# R451X.net
KiCad netlist of a schematic drawn in EAGLE
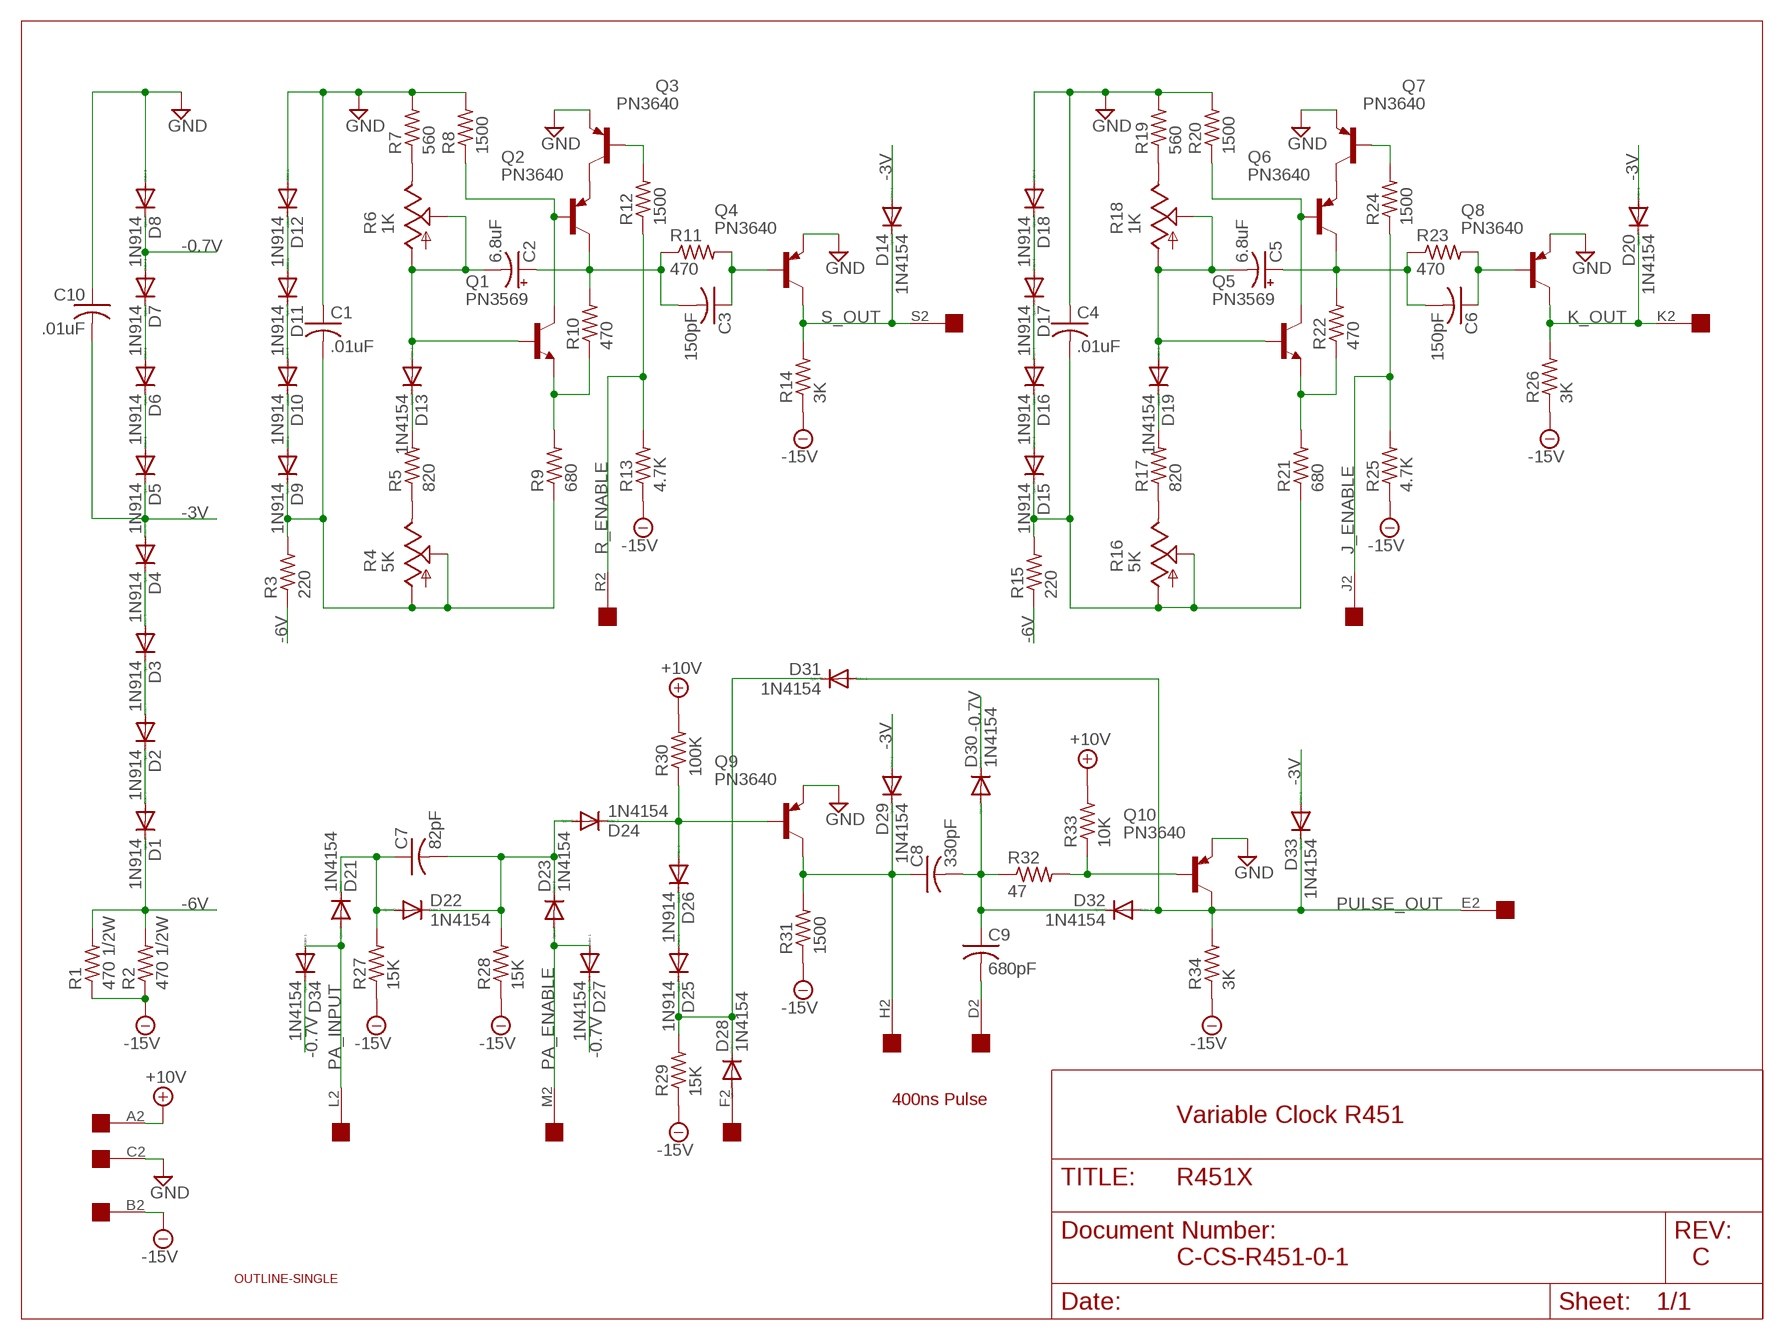
[diagram p0: schematic, sheet 1]

(export (version "E")
  (design (tool "Eeschema 10.0.6"))
  (components
    (comp (ref "C1")
      (value ".01uF")
      (footprint "eagle-import:C050-025X075")
      (libsource (lib "eagle-import") (part "C-US050-025X075"))
    )
    (comp (ref "C2")
      (value "6.8uF")
      (footprint "eagle-import:E12-4")
      (libsource (lib "eagle-import") (part "CPOL-USE12-4AXIAL"))
    )
    (comp (ref "C3")
      (value "150pF")
      (footprint "eagle-import:C075-032X103")
      (libsource (lib "eagle-import") (part "C-US075-032X103"))
    )
    (comp (ref "C4")
      (value ".01uF")
      (footprint "eagle-import:C050-025X075")
      (libsource (lib "eagle-import") (part "C-US050-025X075"))
    )
    (comp (ref "C5")
      (value "6.8uF")
      (footprint "eagle-import:E12-4")
      (libsource (lib "eagle-import") (part "CPOL-USE12-4AXIAL"))
    )
    (comp (ref "C6")
      (value "150pF")
      (footprint "eagle-import:C075-032X103")
      (libsource (lib "eagle-import") (part "C-US075-032X103"))
    )
    (comp (ref "C7")
      (value "82pF")
      (footprint "eagle-import:C075-032X103")
      (libsource (lib "eagle-import") (part "C-US075-032X103"))
    )
    (comp (ref "C8")
      (value "330pF")
      (footprint "eagle-import:C075-032X103")
      (libsource (lib "eagle-import") (part "C-US075-032X103"))
    )
    (comp (ref "C9")
      (value "680pF")
      (footprint "eagle-import:C075-032X103")
      (libsource (lib "eagle-import") (part "C-US075-032X103"))
    )
    (comp (ref "C10")
      (value ".01uF")
      (footprint "eagle-import:C050-025X075")
      (libsource (lib "eagle-import") (part "C-US050-025X075"))
    )
    (comp (ref "D1")
      (value "1N914")
      (footprint "eagle-import:DO35-10")
      (libsource (lib "eagle-import") (part "1N4148DO35-10"))
    )
    (comp (ref "D2")
      (value "1N914")
      (footprint "eagle-import:DO35-10")
      (libsource (lib "eagle-import") (part "1N4148DO35-10"))
    )
    (comp (ref "D3")
      (value "1N914")
      (footprint "eagle-import:DO35-10")
      (libsource (lib "eagle-import") (part "1N4148DO35-10"))
    )
    (comp (ref "D4")
      (value "1N914")
      (footprint "eagle-import:DO35-10")
      (libsource (lib "eagle-import") (part "1N4148DO35-10"))
    )
    (comp (ref "D5")
      (value "1N914")
      (footprint "eagle-import:DO35-10")
      (libsource (lib "eagle-import") (part "1N4148DO35-10"))
    )
    (comp (ref "D6")
      (value "1N914")
      (footprint "eagle-import:DO35-10")
      (libsource (lib "eagle-import") (part "1N4148DO35-10"))
    )
    (comp (ref "D7")
      (value "1N914")
      (footprint "eagle-import:DO35-10")
      (libsource (lib "eagle-import") (part "1N4148DO35-10"))
    )
    (comp (ref "D8")
      (value "1N914")
      (footprint "eagle-import:DO35-10")
      (libsource (lib "eagle-import") (part "1N4148DO35-10"))
    )
    (comp (ref "D9")
      (value "1N914")
      (footprint "eagle-import:DO35-10")
      (libsource (lib "eagle-import") (part "1N4148DO35-10"))
    )
    (comp (ref "D10")
      (value "1N914")
      (footprint "eagle-import:DO35-10")
      (libsource (lib "eagle-import") (part "1N4148DO35-10"))
    )
    (comp (ref "D11")
      (value "1N914")
      (footprint "eagle-import:DO35-10")
      (libsource (lib "eagle-import") (part "1N4148DO35-10"))
    )
    (comp (ref "D12")
      (value "1N914")
      (footprint "eagle-import:DO35-10")
      (libsource (lib "eagle-import") (part "1N4148DO35-10"))
    )
    (comp (ref "D13")
      (value "1N4154")
      (footprint "eagle-import:DO35-10")
      (libsource (lib "eagle-import") (part "1N4148DO35-10"))
    )
    (comp (ref "D14")
      (value "1N4154")
      (footprint "eagle-import:DO35-10")
      (libsource (lib "eagle-import") (part "1N4148DO35-10"))
    )
    (comp (ref "D15")
      (value "1N914")
      (footprint "eagle-import:DO35-10")
      (libsource (lib "eagle-import") (part "1N4148DO35-10"))
    )
    (comp (ref "D16")
      (value "1N914")
      (footprint "eagle-import:DO35-10")
      (libsource (lib "eagle-import") (part "1N4148DO35-10"))
    )
    (comp (ref "D17")
      (value "1N914")
      (footprint "eagle-import:DO35-10")
      (libsource (lib "eagle-import") (part "1N4148DO35-10"))
    )
    (comp (ref "D18")
      (value "1N914")
      (footprint "eagle-import:DO35-10")
      (libsource (lib "eagle-import") (part "1N4148DO35-10"))
    )
    (comp (ref "D19")
      (value "1N4154")
      (footprint "eagle-import:DO35-10")
      (libsource (lib "eagle-import") (part "1N4148DO35-10"))
    )
    (comp (ref "D20")
      (value "1N4154")
      (footprint "eagle-import:DO35-10")
      (libsource (lib "eagle-import") (part "1N4148DO35-10"))
    )
    (comp (ref "D21")
      (value "1N4154")
      (footprint "eagle-import:DO35-10")
      (libsource (lib "eagle-import") (part "1N4148DO35-10"))
    )
    (comp (ref "D22")
      (value "1N4154")
      (footprint "eagle-import:DO35-10")
      (libsource (lib "eagle-import") (part "1N4148DO35-10"))
    )
    (comp (ref "D23")
      (value "1N4154")
      (footprint "eagle-import:DO35-10")
      (libsource (lib "eagle-import") (part "1N4148DO35-10"))
    )
    (comp (ref "D24")
      (value "1N4154")
      (footprint "eagle-import:DO35-10")
      (libsource (lib "eagle-import") (part "1N4148DO35-10"))
    )
    (comp (ref "D25")
      (value "1N914")
      (footprint "eagle-import:DO35-10")
      (libsource (lib "eagle-import") (part "1N4148DO35-10"))
    )
    (comp (ref "D26")
      (value "1N914")
      (footprint "eagle-import:DO35-10")
      (libsource (lib "eagle-import") (part "1N4148DO35-10"))
    )
    (comp (ref "D27")
      (value "1N4154")
      (footprint "eagle-import:DO35-10")
      (libsource (lib "eagle-import") (part "1N4148DO35-10"))
    )
    (comp (ref "D28")
      (value "1N4154")
      (footprint "eagle-import:DO35-10")
      (libsource (lib "eagle-import") (part "1N4148DO35-10"))
    )
    (comp (ref "D29")
      (value "1N4154")
      (footprint "eagle-import:DO35-10")
      (libsource (lib "eagle-import") (part "1N4148DO35-10"))
    )
    (comp (ref "D30")
      (value "1N4154")
      (footprint "eagle-import:DO35-10")
      (libsource (lib "eagle-import") (part "1N4148DO35-10"))
    )
    (comp (ref "D31")
      (value "1N4154")
      (footprint "eagle-import:DO35-10")
      (libsource (lib "eagle-import") (part "1N4148DO35-10"))
    )
    (comp (ref "D32")
      (value "1N4154")
      (footprint "eagle-import:DO35-10")
      (libsource (lib "eagle-import") (part "1N4148DO35-10"))
    )
    (comp (ref "D33")
      (value "1N4154")
      (footprint "eagle-import:DO35-10")
      (libsource (lib "eagle-import") (part "1N4148DO35-10"))
    )
    (comp (ref "D34")
      (value "1N4154")
      (footprint "eagle-import:DO35-10")
      (libsource (lib "eagle-import") (part "1N4148DO35-10"))
    )
    (comp (ref "Q1")
      (value "PN3569")
      (footprint "eagle-import:TO5")
      (libsource (lib "eagle-import") (part "2N2102"))
    )
    (comp (ref "Q2")
      (value "PN3640")
      (footprint "eagle-import:TO39")
      (libsource (lib "eagle-import") (part "2N2904"))
    )
    (comp (ref "Q3")
      (value "PN3640")
      (footprint "eagle-import:TO39")
      (libsource (lib "eagle-import") (part "2N2904"))
    )
    (comp (ref "Q4")
      (value "PN3640")
      (footprint "eagle-import:TO39")
      (libsource (lib "eagle-import") (part "2N2904"))
    )
    (comp (ref "Q5")
      (value "PN3569")
      (footprint "eagle-import:TO5")
      (libsource (lib "eagle-import") (part "2N2102"))
    )
    (comp (ref "Q6")
      (value "PN3640")
      (footprint "eagle-import:TO39")
      (libsource (lib "eagle-import") (part "2N2904"))
    )
    (comp (ref "Q7")
      (value "PN3640")
      (footprint "eagle-import:TO39")
      (libsource (lib "eagle-import") (part "2N2904"))
    )
    (comp (ref "Q8")
      (value "PN3640")
      (footprint "eagle-import:TO39")
      (libsource (lib "eagle-import") (part "2N2904"))
    )
    (comp (ref "Q9")
      (value "PN3640")
      (footprint "eagle-import:TO39")
      (libsource (lib "eagle-import") (part "2N2904"))
    )
    (comp (ref "Q10")
      (value "PN3640")
      (footprint "eagle-import:TO39")
      (libsource (lib "eagle-import") (part "2N2904"))
    )
    (comp (ref "R1")
      (value "470 1/2W")
      (footprint "eagle-import:0411_15")
      (libsource (lib "eagle-import") (part "R-US_0411/15"))
    )
    (comp (ref "R2")
      (value "470 1/2W")
      (footprint "eagle-import:0411_15")
      (libsource (lib "eagle-import") (part "R-US_0411/15"))
    )
    (comp (ref "R3")
      (value "220")
      (footprint "eagle-import:0207_10")
      (libsource (lib "eagle-import") (part "R-US_0207/10"))
    )
    (comp (ref "R4")
      (value "5K")
      (footprint "eagle-import:CT6")
      (libsource (lib "eagle-import") (part "TRIM_US-CT6"))
    )
    (comp (ref "R5")
      (value "820")
      (footprint "eagle-import:0207_10")
      (libsource (lib "eagle-import") (part "R-US_0207/10"))
    )
    (comp (ref "R6")
      (value "1K")
      (footprint "eagle-import:CT6")
      (libsource (lib "eagle-import") (part "TRIM_US-CT6"))
    )
    (comp (ref "R7")
      (value "560")
      (footprint "eagle-import:0207_10")
      (libsource (lib "eagle-import") (part "R-US_0207/10"))
    )
    (comp (ref "R8")
      (value "1500")
      (footprint "eagle-import:0207_10")
      (libsource (lib "eagle-import") (part "R-US_0207/10"))
    )
    (comp (ref "R9")
      (value "680")
      (footprint "eagle-import:0207_10")
      (libsource (lib "eagle-import") (part "R-US_0207/10"))
    )
    (comp (ref "R10")
      (value "470")
      (footprint "eagle-import:0207_10")
      (libsource (lib "eagle-import") (part "R-US_0207/10"))
    )
    (comp (ref "R11")
      (value "470")
      (footprint "eagle-import:0207_10")
      (libsource (lib "eagle-import") (part "R-US_0207/10"))
    )
    (comp (ref "R12")
      (value "1500")
      (footprint "eagle-import:0207_10")
      (libsource (lib "eagle-import") (part "R-US_0207/10"))
    )
    (comp (ref "R13")
      (value "4.7K")
      (footprint "eagle-import:0207_10")
      (libsource (lib "eagle-import") (part "R-US_0207/10"))
    )
    (comp (ref "R14")
      (value "3K")
      (footprint "eagle-import:0207_10")
      (libsource (lib "eagle-import") (part "R-US_0207/10"))
    )
    (comp (ref "R15")
      (value "220")
      (footprint "eagle-import:0207_10")
      (libsource (lib "eagle-import") (part "R-US_0207/10"))
    )
    (comp (ref "R16")
      (value "5K")
      (footprint "eagle-import:CT6")
      (libsource (lib "eagle-import") (part "TRIM_US-CT6"))
    )
    (comp (ref "R17")
      (value "820")
      (footprint "eagle-import:0207_10")
      (libsource (lib "eagle-import") (part "R-US_0207/10"))
    )
    (comp (ref "R18")
      (value "1K")
      (footprint "eagle-import:CT6")
      (libsource (lib "eagle-import") (part "TRIM_US-CT6"))
    )
    (comp (ref "R19")
      (value "560")
      (footprint "eagle-import:0207_10")
      (libsource (lib "eagle-import") (part "R-US_0207/10"))
    )
    (comp (ref "R20")
      (value "1500")
      (footprint "eagle-import:0207_10")
      (libsource (lib "eagle-import") (part "R-US_0207/10"))
    )
    (comp (ref "R21")
      (value "680")
      (footprint "eagle-import:0207_10")
      (libsource (lib "eagle-import") (part "R-US_0207/10"))
    )
    (comp (ref "R22")
      (value "470")
      (footprint "eagle-import:0207_10")
      (libsource (lib "eagle-import") (part "R-US_0207/10"))
    )
    (comp (ref "R23")
      (value "470")
      (footprint "eagle-import:0207_10")
      (libsource (lib "eagle-import") (part "R-US_0207/10"))
    )
    (comp (ref "R24")
      (value "1500")
      (footprint "eagle-import:0207_10")
      (libsource (lib "eagle-import") (part "R-US_0207/10"))
    )
    (comp (ref "R25")
      (value "4.7K")
      (footprint "eagle-import:0207_10")
      (libsource (lib "eagle-import") (part "R-US_0207/10"))
    )
    (comp (ref "R26")
      (value "3K")
      (footprint "eagle-import:0207_10")
      (libsource (lib "eagle-import") (part "R-US_0207/10"))
    )
    (comp (ref "R27")
      (value "15K")
      (footprint "eagle-import:0207_10")
      (libsource (lib "eagle-import") (part "R-US_0207/10"))
    )
    (comp (ref "R28")
      (value "15K")
      (footprint "eagle-import:0207_10")
      (libsource (lib "eagle-import") (part "R-US_0207/10"))
    )
    (comp (ref "R29")
      (value "15K")
      (footprint "eagle-import:0207_10")
      (libsource (lib "eagle-import") (part "R-US_0207/10"))
    )
    (comp (ref "R30")
      (value "100K")
      (footprint "eagle-import:0207_10")
      (libsource (lib "eagle-import") (part "R-US_0207/10"))
    )
    (comp (ref "R31")
      (value "1500")
      (footprint "eagle-import:0207_10")
      (libsource (lib "eagle-import") (part "R-US_0207/10"))
    )
    (comp (ref "R32")
      (value "47")
      (footprint "eagle-import:0207_10")
      (libsource (lib "eagle-import") (part "R-US_0207/10"))
    )
    (comp (ref "R33")
      (value "10K")
      (footprint "eagle-import:0207_10")
      (libsource (lib "eagle-import") (part "R-US_0207/10"))
    )
    (comp (ref "R34")
      (value "3K")
      (footprint "eagle-import:0207_10")
      (libsource (lib "eagle-import") (part "R-US_0207/10"))
    )
    (comp (ref "U$1")
      (value "OUTLINE-SINGLE")
      (footprint "eagle-import:SINGLE")
      (libsource (lib "eagle-import") (part "OUTLINE-SINGLE"))
    )
    (comp (ref "U$2")
      (value "EDGE-1")
      (footprint "eagle-import:EDGE-CON1")
      (libsource (lib "eagle-import") (part "EDGE-1"))
    )
  )
  (nets
    (net (code "1") (name "+10V") (class "Default")
      (node (ref "R30") (pin "2") (pinfunction "2_2") (pintype "passive"))
      (node (ref "R33") (pin "2") (pinfunction "2_2") (pintype "passive"))
      (node (ref "U$2") (pin "A2") (pinfunction "1_A2") (pintype "bidirectional"))
    )
    (net (code "2") (name "-15V") (class "Default")
      (node (ref "R1") (pin "1") (pinfunction "1_1") (pintype "passive"))
      (node (ref "R13") (pin "1") (pinfunction "1_1") (pintype "passive"))
      (node (ref "R14") (pin "1") (pinfunction "1_1") (pintype "passive"))
      (node (ref "R2") (pin "1") (pinfunction "1_1") (pintype "passive"))
      (node (ref "R25") (pin "1") (pinfunction "1_1") (pintype "passive"))
      (node (ref "R26") (pin "1") (pinfunction "1_1") (pintype "passive"))
      (node (ref "R27") (pin "1") (pinfunction "1_1") (pintype "passive"))
      (node (ref "R28") (pin "1") (pinfunction "1_1") (pintype "passive"))
      (node (ref "R29") (pin "1") (pinfunction "1_1") (pintype "passive"))
      (node (ref "R31") (pin "1") (pinfunction "1_1") (pintype "passive"))
      (node (ref "R34") (pin "1") (pinfunction "1_1") (pintype "passive"))
      (node (ref "U$2") (pin "B2") (pinfunction "1_B2") (pintype "bidirectional"))
    )
    (net (code "3") (name "/-0.7V") (class "Default")
      (node (ref "D27") (pin "C") (pinfunction "C_C") (pintype "passive"))
      (node (ref "D30") (pin "C") (pinfunction "C_C") (pintype "passive"))
      (node (ref "D34") (pin "C") (pinfunction "C_C") (pintype "passive"))
      (node (ref "D7") (pin "A") (pinfunction "A_A") (pintype "passive"))
      (node (ref "D8") (pin "C") (pinfunction "C_C") (pintype "passive"))
    )
    (net (code "4") (name "/-3V") (class "Default")
      (node (ref "C10") (pin "2") (pinfunction "2_2") (pintype "passive"))
      (node (ref "D14") (pin "A") (pinfunction "A_A") (pintype "passive"))
      (node (ref "D20") (pin "A") (pinfunction "A_A") (pintype "passive"))
      (node (ref "D29") (pin "A") (pinfunction "A_A") (pintype "passive"))
      (node (ref "D33") (pin "A") (pinfunction "A_A") (pintype "passive"))
      (node (ref "D4") (pin "A") (pinfunction "A_A") (pintype "passive"))
      (node (ref "D5") (pin "C") (pinfunction "C_C") (pintype "passive"))
    )
    (net (code "5") (name "/-6V") (class "Default")
      (node (ref "D1") (pin "C") (pinfunction "C_C") (pintype "passive"))
      (node (ref "R1") (pin "2") (pinfunction "2_2") (pintype "passive"))
      (node (ref "R15") (pin "1") (pinfunction "1_1") (pintype "passive"))
      (node (ref "R2") (pin "2") (pinfunction "2_2") (pintype "passive"))
      (node (ref "R3") (pin "1") (pinfunction "1_1") (pintype "passive"))
    )
    (net (code "6") (name "/J_ENABLE") (class "Default")
      (node (ref "R24") (pin "1") (pinfunction "1_1") (pintype "passive"))
      (node (ref "R25") (pin "2") (pinfunction "2_2") (pintype "passive"))
      (node (ref "U$2") (pin "J2") (pinfunction "1_J2") (pintype "bidirectional"))
    )
    (net (code "7") (name "/K_OUT") (class "Default")
      (node (ref "D20") (pin "C") (pinfunction "C_C") (pintype "passive"))
      (node (ref "Q8") (pin "3") (pinfunction "C_3") (pintype "passive"))
      (node (ref "R26") (pin "2") (pinfunction "2_2") (pintype "passive"))
      (node (ref "U$2") (pin "K2") (pinfunction "1_K2") (pintype "bidirectional"))
    )
    (net (code "8") (name "/PA_ENABLE") (class "Default")
      (node (ref "D23") (pin "A") (pinfunction "A_A") (pintype "passive"))
      (node (ref "D27") (pin "A") (pinfunction "A_A") (pintype "passive"))
      (node (ref "U$2") (pin "M2") (pinfunction "1_M2") (pintype "bidirectional"))
    )
    (net (code "9") (name "/PA_INPUT") (class "Default")
      (node (ref "D21") (pin "A") (pinfunction "A_A") (pintype "passive"))
      (node (ref "D34") (pin "A") (pinfunction "A_A") (pintype "passive"))
      (node (ref "U$2") (pin "L2") (pinfunction "1_L2") (pintype "bidirectional"))
    )
    (net (code "10") (name "/PULSE_OUT") (class "Default")
      (node (ref "D31") (pin "A") (pinfunction "A_A") (pintype "passive"))
      (node (ref "D32") (pin "A") (pinfunction "A_A") (pintype "passive"))
      (node (ref "D33") (pin "C") (pinfunction "C_C") (pintype "passive"))
      (node (ref "Q10") (pin "3") (pinfunction "C_3") (pintype "passive"))
      (node (ref "R34") (pin "2") (pinfunction "2_2") (pintype "passive"))
      (node (ref "U$2") (pin "E2") (pinfunction "1_E2") (pintype "bidirectional"))
    )
    (net (code "11") (name "/R_ENABLE") (class "Default")
      (node (ref "R12") (pin "1") (pinfunction "1_1") (pintype "passive"))
      (node (ref "R13") (pin "2") (pinfunction "2_2") (pintype "passive"))
      (node (ref "U$2") (pin "R2") (pinfunction "1_R2") (pintype "bidirectional"))
    )
    (net (code "12") (name "/S_OUT") (class "Default")
      (node (ref "D14") (pin "C") (pinfunction "C_C") (pintype "passive"))
      (node (ref "Q4") (pin "3") (pinfunction "C_3") (pintype "passive"))
      (node (ref "R14") (pin "2") (pinfunction "2_2") (pintype "passive"))
      (node (ref "U$2") (pin "S2") (pinfunction "1_S2") (pintype "bidirectional"))
    )
    (net (code "13") (name "GND") (class "Default")
      (node (ref "C1") (pin "1") (pinfunction "1_1") (pintype "passive"))
      (node (ref "C10") (pin "1") (pinfunction "1_1") (pintype "passive"))
      (node (ref "C4") (pin "1") (pinfunction "1_1") (pintype "passive"))
      (node (ref "D12") (pin "A") (pinfunction "A_A") (pintype "passive"))
      (node (ref "D18") (pin "A") (pinfunction "A_A") (pintype "passive"))
      (node (ref "D8") (pin "A") (pinfunction "A_A") (pintype "passive"))
      (node (ref "Q10") (pin "1") (pinfunction "E_1") (pintype "passive"))
      (node (ref "Q3") (pin "1") (pinfunction "E_1") (pintype "passive"))
      (node (ref "Q4") (pin "1") (pinfunction "E_1") (pintype "passive"))
      (node (ref "Q7") (pin "1") (pinfunction "E_1") (pintype "passive"))
      (node (ref "Q8") (pin "1") (pinfunction "E_1") (pintype "passive"))
      (node (ref "Q9") (pin "1") (pinfunction "E_1") (pintype "passive"))
      (node (ref "R19") (pin "2") (pinfunction "2_2") (pintype "passive"))
      (node (ref "R20") (pin "2") (pinfunction "2_2") (pintype "passive"))
      (node (ref "R7") (pin "2") (pinfunction "2_2") (pintype "passive"))
      (node (ref "R8") (pin "2") (pinfunction "2_2") (pintype "passive"))
      (node (ref "U$2") (pin "C2") (pinfunction "1_C2") (pintype "bidirectional"))
    )
    (net (code "14") (name "Net-(C1-Pad2)") (class "Default")
      (node (ref "C1") (pin "2") (pinfunction "2_2") (pintype "passive"))
      (node (ref "D9") (pin "C") (pinfunction "C_C") (pintype "passive"))
      (node (ref "R3") (pin "2") (pinfunction "2_2") (pintype "passive"))
      (node (ref "R4") (pin "A") (pinfunction "A_A") (pintype "passive"))
      (node (ref "R4") (pin "S") (pinfunction "S_S") (pintype "passive"))
      (node (ref "R9") (pin "1") (pinfunction "1_1") (pintype "passive"))
    )
    (net (code "15") (name "Net-(C4-Pad2)") (class "Default")
      (node (ref "C4") (pin "2") (pinfunction "2_2") (pintype "passive"))
      (node (ref "D15") (pin "C") (pinfunction "C_C") (pintype "passive"))
      (node (ref "R15") (pin "2") (pinfunction "2_2") (pintype "passive"))
      (node (ref "R16") (pin "A") (pinfunction "A_A") (pintype "passive"))
      (node (ref "R16") (pin "S") (pinfunction "S_S") (pintype "passive"))
      (node (ref "R21") (pin "1") (pinfunction "1_1") (pintype "passive"))
    )
    (net (code "16") (name "Net-(C7-Pad1)") (class "Default")
      (node (ref "C7") (pin "1") (pinfunction "1_1") (pintype "passive"))
      (node (ref "D21") (pin "C") (pinfunction "C_C") (pintype "passive"))
      (node (ref "D22") (pin "A") (pinfunction "A_A") (pintype "passive"))
      (node (ref "R27") (pin "2") (pinfunction "2_2") (pintype "passive"))
    )
    (net (code "17") (name "Net-(C7-Pad2)") (class "Default")
      (node (ref "C7") (pin "2") (pinfunction "2_2") (pintype "passive"))
      (node (ref "D22") (pin "C") (pinfunction "C_C") (pintype "passive"))
      (node (ref "D23") (pin "C") (pinfunction "C_C") (pintype "passive"))
      (node (ref "D24") (pin "A") (pinfunction "A_A") (pintype "passive"))
      (node (ref "R28") (pin "2") (pinfunction "2_2") (pintype "passive"))
    )
    (net (code "18") (name "Net-(C8-Pad2)") (class "Default")
      (node (ref "C8") (pin "2") (pinfunction "2_2") (pintype "passive"))
      (node (ref "C9") (pin "1") (pinfunction "1_1") (pintype "passive"))
      (node (ref "D30") (pin "A") (pinfunction "A_A") (pintype "passive"))
      (node (ref "D32") (pin "C") (pinfunction "C_C") (pintype "passive"))
      (node (ref "R32") (pin "1") (pinfunction "1_1") (pintype "passive"))
    )
    (net (code "19") (name "Net-(D1-PadA)") (class "Default")
      (node (ref "D1") (pin "A") (pinfunction "A_A") (pintype "passive"))
      (node (ref "D2") (pin "C") (pinfunction "C_C") (pintype "passive"))
    )
    (net (code "20") (name "Net-(D2-PadA)") (class "Default")
      (node (ref "D2") (pin "A") (pinfunction "A_A") (pintype "passive"))
      (node (ref "D3") (pin "C") (pinfunction "C_C") (pintype "passive"))
    )
    (net (code "21") (name "Net-(D3-PadA)") (class "Default")
      (node (ref "D3") (pin "A") (pinfunction "A_A") (pintype "passive"))
      (node (ref "D4") (pin "C") (pinfunction "C_C") (pintype "passive"))
    )
    (net (code "22") (name "Net-(D5-PadA)") (class "Default")
      (node (ref "D5") (pin "A") (pinfunction "A_A") (pintype "passive"))
      (node (ref "D6") (pin "C") (pinfunction "C_C") (pintype "passive"))
    )
    (net (code "23") (name "Net-(D6-PadA)") (class "Default")
      (node (ref "D6") (pin "A") (pinfunction "A_A") (pintype "passive"))
      (node (ref "D7") (pin "C") (pinfunction "C_C") (pintype "passive"))
    )
    (net (code "24") (name "Net-(D10-PadA)") (class "Default")
      (node (ref "D10") (pin "A") (pinfunction "A_A") (pintype "passive"))
      (node (ref "D11") (pin "C") (pinfunction "C_C") (pintype "passive"))
    )
    (net (code "25") (name "Net-(D10-PadC)") (class "Default")
      (node (ref "D10") (pin "C") (pinfunction "C_C") (pintype "passive"))
      (node (ref "D9") (pin "A") (pinfunction "A_A") (pintype "passive"))
    )
    (net (code "26") (name "Net-(D11-PadA)") (class "Default")
      (node (ref "D11") (pin "A") (pinfunction "A_A") (pintype "passive"))
      (node (ref "D12") (pin "C") (pinfunction "C_C") (pintype "passive"))
    )
    (net (code "27") (name "Net-(D13-PadC)") (class "Default")
      (node (ref "D13") (pin "C") (pinfunction "C_C") (pintype "passive"))
      (node (ref "R5") (pin "2") (pinfunction "2_2") (pintype "passive"))
    )
    (net (code "28") (name "Net-(D15-PadA)") (class "Default")
      (node (ref "D15") (pin "A") (pinfunction "A_A") (pintype "passive"))
      (node (ref "D16") (pin "C") (pinfunction "C_C") (pintype "passive"))
    )
    (net (code "29") (name "Net-(D16-PadA)") (class "Default")
      (node (ref "D16") (pin "A") (pinfunction "A_A") (pintype "passive"))
      (node (ref "D17") (pin "C") (pinfunction "C_C") (pintype "passive"))
    )
    (net (code "30") (name "Net-(D17-PadA)") (class "Default")
      (node (ref "D17") (pin "A") (pinfunction "A_A") (pintype "passive"))
      (node (ref "D18") (pin "C") (pinfunction "C_C") (pintype "passive"))
    )
    (net (code "31") (name "Net-(D19-PadC)") (class "Default")
      (node (ref "D19") (pin "C") (pinfunction "C_C") (pintype "passive"))
      (node (ref "R17") (pin "2") (pinfunction "2_2") (pintype "passive"))
    )
    (net (code "32") (name "Net-(D25-PadA)") (class "Default")
      (node (ref "D25") (pin "A") (pinfunction "A_A") (pintype "passive"))
      (node (ref "D26") (pin "C") (pinfunction "C_C") (pintype "passive"))
    )
    (net (code "33") (name "Net-(D25-PadC)") (class "Default")
      (node (ref "D25") (pin "C") (pinfunction "C_C") (pintype "passive"))
      (node (ref "D28") (pin "C") (pinfunction "C_C") (pintype "passive"))
      (node (ref "D31") (pin "C") (pinfunction "C_C") (pintype "passive"))
      (node (ref "R29") (pin "2") (pinfunction "2_2") (pintype "passive"))
    )
    (net (code "34") (name "Net-(Q1-B)") (class "Default")
      (node (ref "C2") (pin "-") (pinfunction "-_-") (pintype "passive"))
      (node (ref "D13") (pin "A") (pinfunction "A_A") (pintype "passive"))
      (node (ref "Q1") (pin "2") (pinfunction "B_2") (pintype "passive"))
      (node (ref "R6") (pin "A") (pinfunction "A_A") (pintype "passive"))
      (node (ref "R6") (pin "S") (pinfunction "S_S") (pintype "passive"))
    )
    (net (code "35") (name "Net-(Q1-C)") (class "Default")
      (node (ref "Q1") (pin "3") (pinfunction "C_3") (pintype "passive"))
      (node (ref "Q2") (pin "2") (pinfunction "B_2") (pintype "passive"))
      (node (ref "R8") (pin "1") (pinfunction "1_1") (pintype "passive"))
    )
    (net (code "36") (name "Net-(Q1-E)") (class "Default")
      (node (ref "Q1") (pin "1") (pinfunction "E_1") (pintype "passive"))
      (node (ref "R10") (pin "1") (pinfunction "1_1") (pintype "passive"))
      (node (ref "R9") (pin "2") (pinfunction "2_2") (pintype "passive"))
    )
    (net (code "37") (name "Net-(Q2-C)") (class "Default")
      (node (ref "C2") (pin "+") (pinfunction "+_+") (pintype "passive"))
      (node (ref "C3") (pin "2") (pinfunction "2_2") (pintype "passive"))
      (node (ref "Q2") (pin "3") (pinfunction "C_3") (pintype "passive"))
      (node (ref "R10") (pin "2") (pinfunction "2_2") (pintype "passive"))
      (node (ref "R11") (pin "1") (pinfunction "1_1") (pintype "passive"))
    )
    (net (code "38") (name "Net-(Q2-E)") (class "Default")
      (node (ref "Q2") (pin "1") (pinfunction "E_1") (pintype "passive"))
      (node (ref "Q3") (pin "3") (pinfunction "C_3") (pintype "passive"))
    )
    (net (code "39") (name "Net-(Q3-B)") (class "Default")
      (node (ref "Q3") (pin "2") (pinfunction "B_2") (pintype "passive"))
      (node (ref "R12") (pin "2") (pinfunction "2_2") (pintype "passive"))
    )
    (net (code "40") (name "Net-(Q4-B)") (class "Default")
      (node (ref "C3") (pin "1") (pinfunction "1_1") (pintype "passive"))
      (node (ref "Q4") (pin "2") (pinfunction "B_2") (pintype "passive"))
      (node (ref "R11") (pin "2") (pinfunction "2_2") (pintype "passive"))
    )
    (net (code "41") (name "Net-(Q5-B)") (class "Default")
      (node (ref "C5") (pin "-") (pinfunction "-_-") (pintype "passive"))
      (node (ref "D19") (pin "A") (pinfunction "A_A") (pintype "passive"))
      (node (ref "Q5") (pin "2") (pinfunction "B_2") (pintype "passive"))
      (node (ref "R18") (pin "A") (pinfunction "A_A") (pintype "passive"))
      (node (ref "R18") (pin "S") (pinfunction "S_S") (pintype "passive"))
    )
    (net (code "42") (name "Net-(Q5-C)") (class "Default")
      (node (ref "Q5") (pin "3") (pinfunction "C_3") (pintype "passive"))
      (node (ref "Q6") (pin "2") (pinfunction "B_2") (pintype "passive"))
      (node (ref "R20") (pin "1") (pinfunction "1_1") (pintype "passive"))
    )
    (net (code "43") (name "Net-(Q5-E)") (class "Default")
      (node (ref "Q5") (pin "1") (pinfunction "E_1") (pintype "passive"))
      (node (ref "R21") (pin "2") (pinfunction "2_2") (pintype "passive"))
      (node (ref "R22") (pin "1") (pinfunction "1_1") (pintype "passive"))
    )
    (net (code "44") (name "Net-(Q6-C)") (class "Default")
      (node (ref "C5") (pin "+") (pinfunction "+_+") (pintype "passive"))
      (node (ref "C6") (pin "2") (pinfunction "2_2") (pintype "passive"))
      (node (ref "Q6") (pin "3") (pinfunction "C_3") (pintype "passive"))
      (node (ref "R22") (pin "2") (pinfunction "2_2") (pintype "passive"))
      (node (ref "R23") (pin "1") (pinfunction "1_1") (pintype "passive"))
    )
    (net (code "45") (name "Net-(Q6-E)") (class "Default")
      (node (ref "Q6") (pin "1") (pinfunction "E_1") (pintype "passive"))
      (node (ref "Q7") (pin "3") (pinfunction "C_3") (pintype "passive"))
    )
    (net (code "46") (name "Net-(Q7-B)") (class "Default")
      (node (ref "Q7") (pin "2") (pinfunction "B_2") (pintype "passive"))
      (node (ref "R24") (pin "2") (pinfunction "2_2") (pintype "passive"))
    )
    (net (code "47") (name "Net-(Q8-B)") (class "Default")
      (node (ref "C6") (pin "1") (pinfunction "1_1") (pintype "passive"))
      (node (ref "Q8") (pin "2") (pinfunction "B_2") (pintype "passive"))
      (node (ref "R23") (pin "2") (pinfunction "2_2") (pintype "passive"))
    )
    (net (code "48") (name "Net-(Q9-B)") (class "Default")
      (node (ref "D24") (pin "C") (pinfunction "C_C") (pintype "passive"))
      (node (ref "D26") (pin "A") (pinfunction "A_A") (pintype "passive"))
      (node (ref "Q9") (pin "2") (pinfunction "B_2") (pintype "passive"))
      (node (ref "R30") (pin "1") (pinfunction "1_1") (pintype "passive"))
    )
    (net (code "49") (name "Net-(Q9-C)") (class "Default")
      (node (ref "C8") (pin "1") (pinfunction "1_1") (pintype "passive"))
      (node (ref "D29") (pin "C") (pinfunction "C_C") (pintype "passive"))
      (node (ref "Q9") (pin "3") (pinfunction "C_3") (pintype "passive"))
      (node (ref "R31") (pin "2") (pinfunction "2_2") (pintype "passive"))
      (node (ref "U$2") (pin "H2") (pinfunction "1_H2") (pintype "bidirectional"))
    )
    (net (code "50") (name "Net-(Q10-B)") (class "Default")
      (node (ref "Q10") (pin "2") (pinfunction "B_2") (pintype "passive"))
      (node (ref "R32") (pin "2") (pinfunction "2_2") (pintype "passive"))
      (node (ref "R33") (pin "1") (pinfunction "1_1") (pintype "passive"))
    )
    (net (code "51") (name "Net-(R4-PadE)") (class "Default")
      (node (ref "R4") (pin "E") (pinfunction "E_E") (pintype "passive"))
      (node (ref "R5") (pin "1") (pinfunction "1_1") (pintype "passive"))
    )
    (net (code "52") (name "Net-(R6-PadE)") (class "Default")
      (node (ref "R6") (pin "E") (pinfunction "E_E") (pintype "passive"))
      (node (ref "R7") (pin "1") (pinfunction "1_1") (pintype "passive"))
    )
    (net (code "53") (name "Net-(R16-PadE)") (class "Default")
      (node (ref "R16") (pin "E") (pinfunction "E_E") (pintype "passive"))
      (node (ref "R17") (pin "1") (pinfunction "1_1") (pintype "passive"))
    )
    (net (code "54") (name "Net-(R18-PadE)") (class "Default")
      (node (ref "R18") (pin "E") (pinfunction "E_E") (pintype "passive"))
      (node (ref "R19") (pin "1") (pinfunction "1_1") (pintype "passive"))
    )
    (net (code "55") (name "Net-(U$2D-1)") (class "Default")
      (node (ref "C9") (pin "2") (pinfunction "2_2") (pintype "passive"))
      (node (ref "U$2") (pin "D2") (pinfunction "1_D2") (pintype "bidirectional"))
    )
    (net (code "56") (name "Net-(U$2F-1)") (class "Default")
      (node (ref "D28") (pin "A") (pinfunction "A_A") (pintype "passive"))
      (node (ref "U$2") (pin "F2") (pinfunction "1_F2") (pintype "bidirectional"))
    )
  )
)
